# ESP32_SCH.net
KiCad netlist of a schematic drawn in Altium Designer
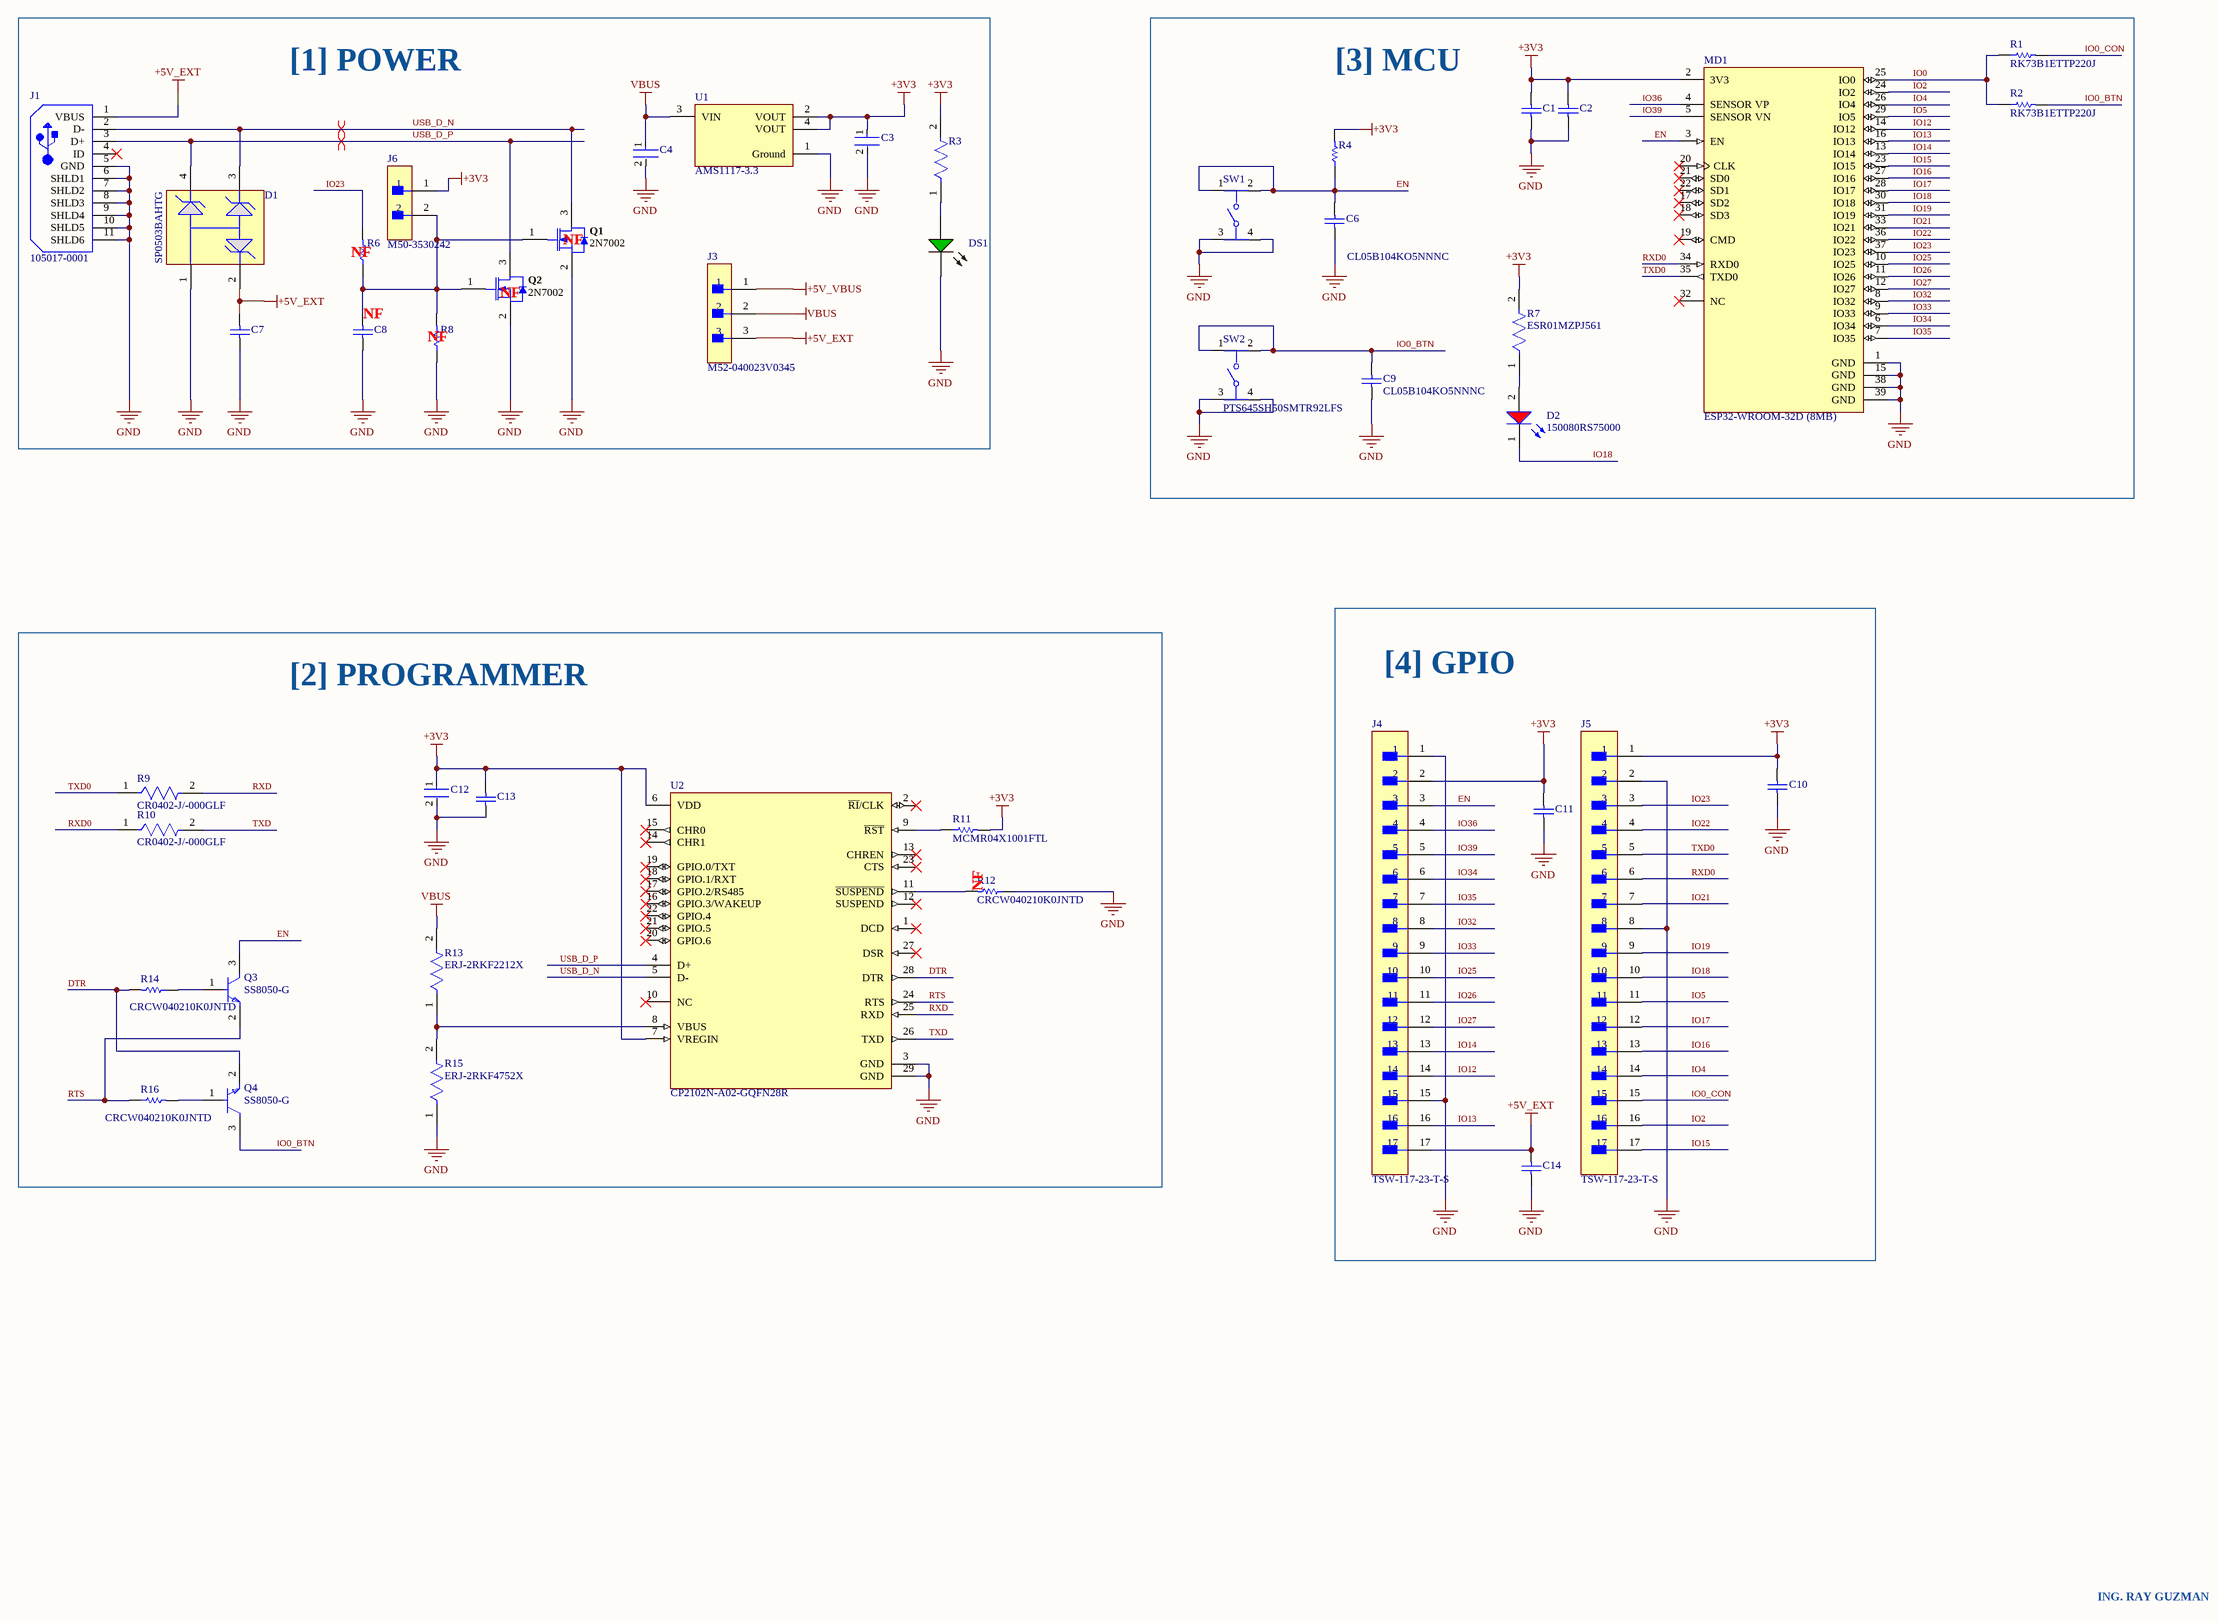
[diagram p0: ESP32_SCH.SchDoc]

(export (version "E")
  (design (tool "Eeschema 10.0.6"))
  (components
    (comp (ref "C1")
      (value "CL21A226MAQNNNE")
      (footprint "CAPC2013X140X45LL15T25")
      (description "Multi-layer Ceramic Capacitor, 22 uF, -55 to 85 degC, 2-Pin SMD (0805), RoHS, Tape and Reel")
      (fields (field (name "MANUFACTURER") "Samsung Electro-Mechanics") (field (name "TOLERANCE") "±20%"))
      (libsource (lib "Altium Content Vault") (part "CAP-NP-2"))
    )
    (comp (ref "C2")
      (value "CL05B104KO5NNNC")
      (footprint "CAPC1050X55X23ML05T13")
      (description "Chip Capacitor, 100 nF, +/- 10%, 16 V, -55 to 125 degC, 0402 (1005 Metric), RoHS, Tape and Reel")
      (fields (field (name "MANUFACTURER") "Samsung Electro-Mechanics"))
      (libsource (lib "Altium Content Vault") (part "CAP-NP-2"))
    )
    (comp (ref "C3")
      (value "CL05A106MP5NUNC")
      (footprint "FP-CL05A106MP5NUNC-MFG")
      (description "CAP CER 10UF 10V X5R 0402")
      (fields
        (field (name "OCTOPART") "https://octopart.com/cl05a106mp5nunc-samsung-22457395")
        (field (name "TOLERANCE") "20%")
      )
      (libsource (lib "Altium Content Vault") (part "b4654b650e69147ec39a6b967a45e02"))
    )
    (comp (ref "C4")
      (value "CL05A106MP5NUNC")
      (footprint "FP-CL05A106MP5NUNC-MFG")
      (description "CAP CER 10UF 10V X5R 0402")
      (fields
        (field (name "OCTOPART") "https://octopart.com/cl05a106mp5nunc-samsung-22457395")
        (field (name "TOLERANCE") "20%")
      )
      (libsource (lib "Altium Content Vault") (part "b4654b650e69147ec39a6b967a45e02"))
    )
    (comp (ref "C6")
      (value "CL05B104KO5NNNC")
      (footprint "CAPC1050X55X23ML05T13")
      (description "Chip Capacitor, 100 nF, +/- 10%, 16 V, -55 to 125 degC, 0402 (1005 Metric), RoHS, Tape and Reel")
      (fields (field (name "MANUFACTURER") "Samsung Electro-Mechanics"))
      (libsource (lib "Altium Content Vault") (part "CAP-NP-2"))
    )
    (comp (ref "C7")
      (value "CL05B104KO5NNNC")
      (footprint "CAPC1050X55X23ML05T13")
      (description "Chip Capacitor, 100 nF, +/- 10%, 16 V, -55 to 125 degC, 0402 (1005 Metric), RoHS, Tape and Reel")
      (fields (field (name "MANUFACTURER") "Samsung Electro-Mechanics"))
      (libsource (lib "Altium Content Vault") (part "CAP-NP-2"))
    )
    (comp (ref "C8")
      (value "CL05B104KO5NNNC")
      (footprint "CAPC1050X55X23ML05T13")
      (description "Chip Capacitor, 100 nF, +/- 10%, 16 V, -55 to 125 degC, 0402 (1005 Metric), RoHS, Tape and Reel")
      (fields (field (name "MANUFACTURER") "Samsung Electro-Mechanics"))
      (libsource (lib "Altium Content Vault") (part "CAP-NP-2"))
    )
    (comp (ref "C9")
      (value "CL05B104KO5NNNC")
      (footprint "CAPC1050X55X23ML05T13")
      (description "Chip Capacitor, 100 nF, +/- 10%, 16 V, -55 to 125 degC, 0402 (1005 Metric), RoHS, Tape and Reel")
      (fields (field (name "MANUFACTURER") "Samsung Electro-Mechanics"))
      (libsource (lib "Altium Content Vault") (part "CAP-NP-2"))
    )
    (comp (ref "C10")
      (value "CL05B104KO5NNNC")
      (footprint "CAPC1050X55X23ML05T13")
      (description "Chip Capacitor, 100 nF, +/- 10%, 16 V, -55 to 125 degC, 0402 (1005 Metric), RoHS, Tape and Reel")
      (fields (field (name "MANUFACTURER") "Samsung Electro-Mechanics"))
      (libsource (lib "Altium Content Vault") (part "CAP-NP-2"))
    )
    (comp (ref "C11")
      (value "CL05B104KO5NNNC")
      (footprint "CAPC1050X55X23ML05T13")
      (description "Chip Capacitor, 100 nF, +/- 10%, 16 V, -55 to 125 degC, 0402 (1005 Metric), RoHS, Tape and Reel")
      (fields (field (name "MANUFACTURER") "Samsung Electro-Mechanics"))
      (libsource (lib "Altium Content Vault") (part "CAP-NP-2"))
    )
    (comp (ref "C12")
      (value "C1005X5R1A475K050BC")
      (footprint "FP-C1005-050-0_15-MFG")
      (description "CAP CER 4.7UF 10V X5R 0402")
      (fields (field (name "TOLERANCE") "10%"))
      (libsource (lib "Altium Content Vault") (part "b4654b650e69147ec39a6b967a45e02"))
    )
    (comp (ref "C13")
      (value "CL05B104KO5NNNC")
      (footprint "CAPC1050X55X23ML05T13")
      (description "Chip Capacitor, 100 nF, +/- 10%, 16 V, -55 to 125 degC, 0402 (1005 Metric), RoHS, Tape and Reel")
      (fields (field (name "MANUFACTURER") "Samsung Electro-Mechanics"))
      (libsource (lib "Altium Content Vault") (part "CAP-NP-2"))
    )
    (comp (ref "C14")
      (value "CL05B104KO5NNNC")
      (footprint "CAPC1050X55X23ML05T13")
      (description "Chip Capacitor, 100 nF, +/- 10%, 16 V, -55 to 125 degC, 0402 (1005 Metric), RoHS, Tape and Reel")
      (fields (field (name "MANUFACTURER") "Samsung Electro-Mechanics"))
      (libsource (lib "Altium Content Vault") (part "CAP-NP-2"))
    )
    (comp (ref "D1")
      (value "SP0503BAHTG")
      (footprint "LFUS-SOT143-4_V")
      (description "TVS Diode Array, 30 pF, 30 KV, -40 to 85 degC, 4-Pin SOT143, RoHS, Tape and Reel")
      (fields (field (name "MANUFACTURER") "Littelfuse"))
      (libsource (lib "Altium Content Vault") (part "LFUS-SP0503BAHTG-SOT143-4"))
    )
    (comp (ref "D2")
      (value "150080RS75000")
      (footprint "WL-SMCW_0805_150080xx75000")
      (libsource (lib "Altium Content Vault") (part "LED_Red_2A-1K"))
    )
    (comp (ref "DS1")
      (value "HSMG-C170")
      (footprint "AVAG-HSMX-C170_V")
      (description "Chip LED, Green, 2.2 V, -40 to 85 degC, 2-Pin SMD, Pb-Free, Tape and Reel")
      (fields (field (name "MANUFACTURER") "Avago"))
      (libsource (lib "Altium Content Vault") (part "LED_GREEN_A1K2-2"))
    )
    (comp (ref "J1")
      (value "105017-0001")
      (footprint "USB-MICRO-B_V")
      (fields (field (name "MANUFACTURER") "Molex"))
      (libsource (lib "Altium Content Vault") (part "USB-5-6SHLD"))
    )
    (comp (ref "J3")
      (value "M52-040023V0345")
      (footprint "FP-M52-040023V0345-MFG")
      (description "CONN HEADER VERT 3POS 1.27MM")
      (libsource (lib "Altium Content Vault") (part "d6a96a410146d2d686cfe982f2af7ec"))
    )
    (comp (ref "J4")
      (value "TSW-117-23-T-S")
      (footprint "FP-TSW-117-23-T-S-MFG")
      (description "CONN HEADER VERT 17POS 2.54MM")
      (libsource (lib "Altium Content Vault") (part "0c150866fb6c9bc24cbcca335282b40"))
    )
    (comp (ref "J5")
      (value "TSW-117-23-T-S")
      (footprint "FP-TSW-117-23-T-S-MFG")
      (description "CONN HEADER VERT 17POS 2.54MM")
      (libsource (lib "Altium Content Vault") (part "0c150866fb6c9bc24cbcca335282b40"))
    )
    (comp (ref "J6")
      (value "M50-3530242")
      (footprint "FP-M50-3530242-MFG")
      (description "CONN HEADER VERT 2POS 1.27MM")
      (libsource (lib "Altium Content Vault") (part "3bc925449376181038e59eaffc5286c"))
    )
    (comp (ref "MD1")
      (value "ESP32-WROOM-32D (8MB)")
      (footprint "FP-ESP32-WROOM-32D_8MB-MFG")
      (description "RX TXRX MOD WIFI TRACE ANT SMD")
      (libsource (lib "Altium Content Vault") (part "f49400bffd2bcd917121b26d8c3f628"))
    )
    (comp (ref "Q1")
      (value "2N7002")
      (footprint "INF-PG-SOT23_M")
      (fields (field (name "MANUFACTURER") "Infineon"))
      (libsource (lib "Altium Content Vault") (part "INF-NDMOS-GSD-3"))
    )
    (comp (ref "Q2")
      (value "2N7002")
      (footprint "INF-PG-SOT23_M")
      (fields (field (name "MANUFACTURER") "Infineon"))
      (libsource (lib "Altium Content Vault") (part "INF-NDMOS-GSD-3"))
    )
    (comp (ref "Q3")
      (value "SS8050-G")
      (footprint "FP-SS8050-G-MFG")
      (description "NPN TRANSISTOR 1.5A 40V SOT-23 R")
      (libsource (lib "Altium Content Vault") (part "2a1388f82443b098dcd57d24ac7632d"))
    )
    (comp (ref "Q4")
      (value "SS8050-G")
      (footprint "FP-SS8050-G-MFG")
      (description "NPN TRANSISTOR 1.5A 40V SOT-23 R")
      (libsource (lib "Altium Content Vault") (part "2a1388f82443b098dcd57d24ac7632d"))
    )
    (comp (ref "R1")
      (value "RK73B1ETTP220J")
      (footprint "RESC1005X40X25ML10T10")
      (fields (field (name "MANUFACTURER") "KOA Speer"))
      (libsource (lib "Altium Content Vault") (part "RES"))
    )
    (comp (ref "R2")
      (value "RK73B1ETTP220J")
      (footprint "RESC1005X40X25ML10T10")
      (fields (field (name "MANUFACTURER") "KOA Speer"))
      (libsource (lib "Altium Content Vault") (part "RES"))
    )
    (comp (ref "R3")
      (value "PNM0402E5001BST1")
      (footprint "FP-PNM0402-IPC_C")
      (description "RES SMD 5K OHM 0.1% 1/20W 0402")
      (fields (field (name "TOLERANCE") "0.1%"))
      (libsource (lib "Altium Content Vault") (part "1029c3af85768c4190bb7ad29bc67b5"))
    )
    (comp (ref "R4")
      (value "CRCW040210K0JNTD")
      (footprint "RESC1005X40X25ML05T05")
      (fields (field (name "MANUFACTURER") "Vishay Dale"))
      (libsource (lib "Altium Content Vault") (part "RES"))
    )
    (comp (ref "R6")
      (value "MCMR04X1001FTL")
      (footprint "RESC1005X40X25ML05T10")
      (fields (field (name "MANUFACTURER") "Multicomp"))
      (libsource (lib "Altium Content Vault") (part "RES"))
    )
    (comp (ref "R7")
      (value "ESR01MZPJ561")
      (footprint "FP-ESR01-IPC_C")
      (description "560Ω ±5% 0.2W 0402 Anti-Surge Chip Resistor AEC-Q200")
      (fields (field (name "TOLERANCE") "5%"))
      (libsource (lib "Altium Content Vault") (part "1029c3af85768c4190bb7ad29bc67b5"))
    )
    (comp (ref "R8")
      (value "CRCW040210K0JNTD")
      (footprint "RESC1005X40X25ML05T05")
      (fields (field (name "MANUFACTURER") "Vishay Dale"))
      (libsource (lib "Altium Content Vault") (part "RES"))
    )
    (comp (ref "R9")
      (value "CR0402-J/-000GLF")
      (footprint "FP-CR0402-IPC_B")
      (description "Thick Film Chip Resistors 0402 0Ω 0.0625W 5%")
      (fields (field (name "TOLERANCE") "5%"))
      (libsource (lib "Altium Content Vault") (part "1029c3af85768c4190bb7ad29bc67b5"))
    )
    (comp (ref "R10")
      (value "CR0402-J/-000GLF")
      (footprint "FP-CR0402-IPC_B")
      (description "Thick Film Chip Resistors 0402 0Ω 0.0625W 5%")
      (fields (field (name "TOLERANCE") "5%"))
      (libsource (lib "Altium Content Vault") (part "1029c3af85768c4190bb7ad29bc67b5"))
    )
    (comp (ref "R11")
      (value "MCMR04X1001FTL")
      (footprint "RESC1005X40X25ML05T10")
      (fields (field (name "MANUFACTURER") "Multicomp"))
      (libsource (lib "Altium Content Vault") (part "RES"))
    )
    (comp (ref "R12")
      (value "CRCW040210K0JNTD")
      (footprint "RESC1005X40X25ML05T05")
      (fields (field (name "MANUFACTURER") "Vishay Dale"))
      (libsource (lib "Altium Content Vault") (part "RES"))
    )
    (comp (ref "R13")
      (value "ERJ-2RKF2212X")
      (footprint "FP-ERJ2RK-IPC_C")
      (description "RES SMD 22.1K OHM 1% 1/10W 0402")
      (fields (field (name "TOLERANCE") "1%"))
      (libsource (lib "Altium Content Vault") (part "1029c3af85768c4190bb7ad29bc67b5"))
    )
    (comp (ref "R14")
      (value "CRCW040210K0JNTD")
      (footprint "RESC1005X40X25ML05T05")
      (fields (field (name "MANUFACTURER") "Vishay Dale"))
      (libsource (lib "Altium Content Vault") (part "RES"))
    )
    (comp (ref "R15")
      (value "ERJ-2RKF4752X")
      (footprint "FP-ERJ2RK-IPC_A")
      (description "RES SMD 47.5K OHM 1% 1/10W 0402")
      (fields (field (name "TOLERANCE") "1%"))
      (libsource (lib "Altium Content Vault") (part "1029c3af85768c4190bb7ad29bc67b5"))
    )
    (comp (ref "R16")
      (value "CRCW040210K0JNTD")
      (footprint "RESC1005X40X25ML05T05")
      (fields (field (name "MANUFACTURER") "Vishay Dale"))
      (libsource (lib "Altium Content Vault") (part "RES"))
    )
    (comp (ref "SW1")
      (value "PTS645SH50SMTR92LFS")
      (footprint "FP-PTS645SH50SMTR92LFS-MFG")
      (description "SWITCH TACTILE SPST-NO 0.05A 12V")
      (libsource (lib "Altium Content Vault") (part "1adf0dd01260c80cf25a44bfd6b99ba"))
    )
    (comp (ref "SW2")
      (value "PTS645SH50SMTR92LFS")
      (footprint "FP-PTS645SH50SMTR92LFS-MFG")
      (description "SWITCH TACTILE SPST-NO 0.05A 12V")
      (libsource (lib "Altium Content Vault") (part "1adf0dd01260c80cf25a44bfd6b99ba"))
    )
    (comp (ref "U1")
      (value "AMS1117-3.3")
      (footprint "FP-AMS1117-IPC_C")
      (description "LDO Voltage Regulators 1A, 3.3V")
      (fields
        (field (name "OCTOPART") "https://octopart.com/ams1117-3.3-advanced+monolithic+systems-25899300")
        (field (name "MANUFACTURER") "Advanced Monolithic Systems")
      )
      (libsource (lib "Altium Content Vault") (part "8bdbb5f8e77002000e30dd2845d0354"))
    )
    (comp (ref "U2")
      (value "CP2102N-A02-GQFN28R")
      (footprint "FP-CP2102N-A02-GQFN28R-MFG")
      (description "IC USB TO UART BRIDGE QFN28")
      (libsource (lib "Altium Content Vault") (part "670edaef084fb69d2a747396d70a05e"))
    )
  )
  (nets
    (net (code "1") (name "+3V3") (class "Default")
      (node (ref "C1") (pin "1") (pinfunction "1_1") (pintype "passive"))
      (node (ref "C10") (pin "1") (pinfunction "1_1") (pintype "passive"))
      (node (ref "C11") (pin "1") (pinfunction "1_1") (pintype "passive"))
      (node (ref "C12") (pin "1") (pinfunction "1_1") (pintype "passive"))
      (node (ref "C13") (pin "1") (pinfunction "1_1") (pintype "passive"))
      (node (ref "C2") (pin "1") (pinfunction "1_1") (pintype "passive"))
      (node (ref "C3") (pin "1") (pinfunction "1_1") (pintype "passive"))
      (node (ref "J4") (pin "2") (pinfunction "2_2") (pintype "passive"))
      (node (ref "J5") (pin "1") (pinfunction "1_1") (pintype "passive"))
      (node (ref "J6") (pin "1") (pinfunction "1_1") (pintype "passive"))
      (node (ref "MD1") (pin "2") (pinfunction "3V3_2") (pintype "power_in"))
      (node (ref "R11") (pin "2") (pinfunction "2_2") (pintype "passive"))
      (node (ref "R3") (pin "2") (pinfunction "2_2") (pintype "passive"))
      (node (ref "R4") (pin "2") (pinfunction "2_2") (pintype "passive"))
      (node (ref "R7") (pin "2") (pinfunction "2_2") (pintype "passive"))
      (node (ref "U1") (pin "2") (pinfunction "VOUT_2") (pintype "passive"))
      (node (ref "U1") (pin "4") (pinfunction "VOUT_4") (pintype "passive"))
      (node (ref "U2") (pin "6") (pinfunction "VDD_6") (pintype "power_in"))
      (node (ref "U2") (pin "7") (pinfunction "VREGIN_7") (pintype "input"))
    )
    (net (code "2") (name "+5V_EXT") (class "Default")
      (node (ref "C14") (pin "1") (pinfunction "1_1") (pintype "passive"))
      (node (ref "C7") (pin "1") (pinfunction "1_1") (pintype "passive"))
      (node (ref "D1") (pin "2") (pinfunction "2_2") (pintype "passive"))
      (node (ref "J1") (pin "1") (pinfunction "VBUS_1") (pintype "passive"))
      (node (ref "J3") (pin "3") (pinfunction "3_3") (pintype "passive"))
      (node (ref "J4") (pin "17") (pinfunction "17_17") (pintype "passive"))
    )
    (net (code "3") (name "+5V_VBUS") (class "Default")
      (node (ref "J3") (pin "1") (pinfunction "1_1") (pintype "passive"))
    )
    (net (code "4") (name "/DTR") (class "Default")
      (node (ref "Q4") (pin "2") (pinfunction "E_2") (pintype "passive"))
      (node (ref "R14") (pin "2") (pinfunction "2_2") (pintype "passive"))
      (node (ref "U2") (pin "28") (pinfunction "DTR_28") (pintype "output"))
    )
    (net (code "5") (name "/EN") (class "Default")
      (node (ref "C6") (pin "2") (pinfunction "2_2") (pintype "passive"))
      (node (ref "J4") (pin "3") (pinfunction "3_3") (pintype "passive"))
      (node (ref "MD1") (pin "3") (pinfunction "EN_3") (pintype "input"))
      (node (ref "Q3") (pin "3") (pinfunction "C_3") (pintype "passive"))
      (node (ref "R4") (pin "1") (pinfunction "1_1") (pintype "passive"))
      (node (ref "SW1") (pin "1") (pinfunction "1_1") (pintype "passive"))
      (node (ref "SW1") (pin "2") (pinfunction "2_2") (pintype "passive"))
    )
    (net (code "6") (name "/IO0") (class "Default")
      (node (ref "MD1") (pin "25") (pinfunction "IO0_25") (pintype "bidirectional"))
      (node (ref "R1") (pin "1") (pinfunction "1_1") (pintype "passive"))
      (node (ref "R2") (pin "1") (pinfunction "1_1") (pintype "passive"))
    )
    (net (code "7") (name "/IO0_BTN") (class "Default")
      (node (ref "C9") (pin "2") (pinfunction "2_2") (pintype "passive"))
      (node (ref "Q4") (pin "3") (pinfunction "C_3") (pintype "passive"))
      (node (ref "R2") (pin "2") (pinfunction "2_2") (pintype "passive"))
      (node (ref "SW2") (pin "1") (pinfunction "1_1") (pintype "passive"))
      (node (ref "SW2") (pin "2") (pinfunction "2_2") (pintype "passive"))
    )
    (net (code "8") (name "/IO0_CON") (class "Default")
      (node (ref "J5") (pin "15") (pinfunction "15_15") (pintype "passive"))
      (node (ref "R1") (pin "2") (pinfunction "2_2") (pintype "passive"))
    )
    (net (code "9") (name "/IO2") (class "Default")
      (node (ref "J5") (pin "16") (pinfunction "16_16") (pintype "passive"))
      (node (ref "MD1") (pin "24") (pinfunction "IO2_24") (pintype "bidirectional"))
    )
    (net (code "10") (name "/IO4") (class "Default")
      (node (ref "J5") (pin "14") (pinfunction "14_14") (pintype "passive"))
      (node (ref "MD1") (pin "26") (pinfunction "IO4_26") (pintype "bidirectional"))
    )
    (net (code "11") (name "/IO5") (class "Default")
      (node (ref "J5") (pin "11") (pinfunction "11_11") (pintype "passive"))
      (node (ref "MD1") (pin "29") (pinfunction "IO5_29") (pintype "bidirectional"))
    )
    (net (code "12") (name "/IO12") (class "Default")
      (node (ref "J4") (pin "14") (pinfunction "14_14") (pintype "passive"))
      (node (ref "MD1") (pin "14") (pinfunction "IO12_14") (pintype "bidirectional"))
    )
    (net (code "13") (name "/IO13") (class "Default")
      (node (ref "J4") (pin "16") (pinfunction "16_16") (pintype "passive"))
      (node (ref "MD1") (pin "16") (pinfunction "IO13_16") (pintype "bidirectional"))
    )
    (net (code "14") (name "/IO14") (class "Default")
      (node (ref "J4") (pin "13") (pinfunction "13_13") (pintype "passive"))
      (node (ref "MD1") (pin "13") (pinfunction "IO14_13") (pintype "bidirectional"))
    )
    (net (code "15") (name "/IO15") (class "Default")
      (node (ref "J5") (pin "17") (pinfunction "17_17") (pintype "passive"))
      (node (ref "MD1") (pin "23") (pinfunction "IO15_23") (pintype "bidirectional"))
    )
    (net (code "16") (name "/IO16") (class "Default")
      (node (ref "J5") (pin "13") (pinfunction "13_13") (pintype "passive"))
      (node (ref "MD1") (pin "27") (pinfunction "IO16_27") (pintype "bidirectional"))
    )
    (net (code "17") (name "/IO17") (class "Default")
      (node (ref "J5") (pin "12") (pinfunction "12_12") (pintype "passive"))
      (node (ref "MD1") (pin "28") (pinfunction "IO17_28") (pintype "bidirectional"))
    )
    (net (code "18") (name "/IO18") (class "Default")
      (node (ref "D2") (pin "1") (pinfunction "K_1") (pintype "passive"))
      (node (ref "J5") (pin "10") (pinfunction "10_10") (pintype "passive"))
      (node (ref "MD1") (pin "30") (pinfunction "IO18_30") (pintype "bidirectional"))
    )
    (net (code "19") (name "/IO19") (class "Default")
      (node (ref "J5") (pin "9") (pinfunction "9_9") (pintype "passive"))
      (node (ref "MD1") (pin "31") (pinfunction "IO19_31") (pintype "bidirectional"))
    )
    (net (code "20") (name "/IO21") (class "Default")
      (node (ref "J5") (pin "7") (pinfunction "7_7") (pintype "passive"))
      (node (ref "MD1") (pin "33") (pinfunction "IO21_33") (pintype "bidirectional"))
    )
    (net (code "21") (name "/IO22") (class "Default")
      (node (ref "J5") (pin "4") (pinfunction "4_4") (pintype "passive"))
      (node (ref "MD1") (pin "36") (pinfunction "IO22_36") (pintype "bidirectional"))
    )
    (net (code "22") (name "/IO23") (class "Default")
      (node (ref "J5") (pin "3") (pinfunction "3_3") (pintype "passive"))
      (node (ref "MD1") (pin "37") (pinfunction "IO23_37") (pintype "bidirectional"))
      (node (ref "R6") (pin "2") (pinfunction "2_2") (pintype "passive"))
    )
    (net (code "23") (name "/IO25") (class "Default")
      (node (ref "J4") (pin "10") (pinfunction "10_10") (pintype "passive"))
      (node (ref "MD1") (pin "10") (pinfunction "IO25_10") (pintype "bidirectional"))
    )
    (net (code "24") (name "/IO26") (class "Default")
      (node (ref "J4") (pin "11") (pinfunction "11_11") (pintype "passive"))
      (node (ref "MD1") (pin "11") (pinfunction "IO26_11") (pintype "bidirectional"))
    )
    (net (code "25") (name "/IO27") (class "Default")
      (node (ref "J4") (pin "12") (pinfunction "12_12") (pintype "passive"))
      (node (ref "MD1") (pin "12") (pinfunction "IO27_12") (pintype "bidirectional"))
    )
    (net (code "26") (name "/IO32") (class "Default")
      (node (ref "J4") (pin "8") (pinfunction "8_8") (pintype "passive"))
      (node (ref "MD1") (pin "8") (pinfunction "IO32_8") (pintype "bidirectional"))
    )
    (net (code "27") (name "/IO33") (class "Default")
      (node (ref "J4") (pin "9") (pinfunction "9_9") (pintype "passive"))
      (node (ref "MD1") (pin "9") (pinfunction "IO33_9") (pintype "bidirectional"))
    )
    (net (code "28") (name "/IO34") (class "Default")
      (node (ref "J4") (pin "6") (pinfunction "6_6") (pintype "passive"))
      (node (ref "MD1") (pin "6") (pinfunction "IO34_6") (pintype "bidirectional"))
    )
    (net (code "29") (name "/IO35") (class "Default")
      (node (ref "J4") (pin "7") (pinfunction "7_7") (pintype "passive"))
      (node (ref "MD1") (pin "7") (pinfunction "IO35_7") (pintype "bidirectional"))
    )
    (net (code "30") (name "/IO36") (class "Default")
      (node (ref "J4") (pin "4") (pinfunction "4_4") (pintype "passive"))
      (node (ref "MD1") (pin "4") (pinfunction "SENSOR_VP_4") (pintype "passive"))
    )
    (net (code "31") (name "/IO39") (class "Default")
      (node (ref "J4") (pin "5") (pinfunction "5_5") (pintype "passive"))
      (node (ref "MD1") (pin "5") (pinfunction "SENSOR_VN_5") (pintype "passive"))
    )
    (net (code "32") (name "/RTS") (class "Default")
      (node (ref "Q3") (pin "2") (pinfunction "E_2") (pintype "passive"))
      (node (ref "R16") (pin "1") (pinfunction "1_1") (pintype "passive"))
      (node (ref "U2") (pin "24") (pinfunction "RTS_24") (pintype "output"))
    )
    (net (code "33") (name "/RXD") (class "Default")
      (node (ref "R9") (pin "2") (pinfunction "2_2") (pintype "passive"))
      (node (ref "U2") (pin "25") (pinfunction "RXD_25") (pintype "input"))
    )
    (net (code "34") (name "/RXD0") (class "Default")
      (node (ref "J5") (pin "6") (pinfunction "6_6") (pintype "passive"))
      (node (ref "MD1") (pin "34") (pinfunction "RXD0_34") (pintype "input"))
      (node (ref "R10") (pin "1") (pinfunction "1_1") (pintype "passive"))
    )
    (net (code "35") (name "/TXD") (class "Default")
      (node (ref "R10") (pin "2") (pinfunction "2_2") (pintype "passive"))
      (node (ref "U2") (pin "26") (pinfunction "TXD_26") (pintype "output"))
    )
    (net (code "36") (name "/TXD0") (class "Default")
      (node (ref "J5") (pin "5") (pinfunction "5_5") (pintype "passive"))
      (node (ref "MD1") (pin "35") (pinfunction "TXD0_35") (pintype "output"))
      (node (ref "R9") (pin "1") (pinfunction "1_1") (pintype "passive"))
    )
    (net (code "37") (name "/USB_D_N") (class "Default")
      (node (ref "D1") (pin "3") (pinfunction "3_3") (pintype "passive"))
      (node (ref "J1") (pin "2") (pinfunction "D-_2") (pintype "passive"))
      (node (ref "Q1") (pin "3") (pinfunction "DRAIN_3") (pintype "passive"))
      (node (ref "U2") (pin "5") (pinfunction "D-_5") (pintype "passive"))
    )
    (net (code "38") (name "/USB_D_P") (class "Default")
      (node (ref "D1") (pin "4") (pinfunction "4_4") (pintype "passive"))
      (node (ref "J1") (pin "3") (pinfunction "D+_3") (pintype "passive"))
      (node (ref "Q2") (pin "3") (pinfunction "DRAIN_3") (pintype "passive"))
      (node (ref "U2") (pin "4") (pinfunction "D+_4") (pintype "passive"))
    )
    (net (code "39") (name "GND") (class "Default")
      (node (ref "C1") (pin "2") (pinfunction "2_2") (pintype "passive"))
      (node (ref "C10") (pin "2") (pinfunction "2_2") (pintype "passive"))
      (node (ref "C11") (pin "2") (pinfunction "2_2") (pintype "passive"))
      (node (ref "C12") (pin "2") (pinfunction "2_2") (pintype "passive"))
      (node (ref "C13") (pin "2") (pinfunction "2_2") (pintype "passive"))
      (node (ref "C14") (pin "2") (pinfunction "2_2") (pintype "passive"))
      (node (ref "C2") (pin "2") (pinfunction "2_2") (pintype "passive"))
      (node (ref "C3") (pin "2") (pinfunction "2_2") (pintype "passive"))
      (node (ref "C4") (pin "2") (pinfunction "2_2") (pintype "passive"))
      (node (ref "C6") (pin "1") (pinfunction "1_1") (pintype "passive"))
      (node (ref "C7") (pin "2") (pinfunction "2_2") (pintype "passive"))
      (node (ref "C8") (pin "1") (pinfunction "1_1") (pintype "passive"))
      (node (ref "C9") (pin "1") (pinfunction "1_1") (pintype "passive"))
      (node (ref "D1") (pin "1") (pinfunction "1_1") (pintype "passive"))
      (node (ref "DS1") (pin "2") (pinfunction "K_2") (pintype "passive"))
      (node (ref "J1") (pin "10") (pinfunction "SHLD5_10") (pintype "passive"))
      (node (ref "J1") (pin "11") (pinfunction "SHLD6_11") (pintype "passive"))
      (node (ref "J1") (pin "5") (pinfunction "GND_5") (pintype "passive"))
      (node (ref "J1") (pin "6") (pinfunction "SHLD1_6") (pintype "passive"))
      (node (ref "J1") (pin "7") (pinfunction "SHLD2_7") (pintype "passive"))
      (node (ref "J1") (pin "8") (pinfunction "SHLD3_8") (pintype "passive"))
      (node (ref "J1") (pin "9") (pinfunction "SHLD4_9") (pintype "passive"))
      (node (ref "J4") (pin "1") (pinfunction "1_1") (pintype "passive"))
      (node (ref "J4") (pin "15") (pinfunction "15_15") (pintype "passive"))
      (node (ref "J5") (pin "2") (pinfunction "2_2") (pintype "passive"))
      (node (ref "J5") (pin "8") (pinfunction "8_8") (pintype "passive"))
      (node (ref "MD1") (pin "1") (pinfunction "GND_1") (pintype "power_in"))
      (node (ref "MD1") (pin "15") (pinfunction "GND_15") (pintype "power_in"))
      (node (ref "MD1") (pin "38") (pinfunction "GND_38") (pintype "power_in"))
      (node (ref "MD1") (pin "39") (pinfunction "GND_39") (pintype "power_in"))
      (node (ref "Q1") (pin "2") (pinfunction "SOURCE_2") (pintype "passive"))
      (node (ref "Q2") (pin "2") (pinfunction "SOURCE_2") (pintype "passive"))
      (node (ref "R12") (pin "1") (pinfunction "1_1") (pintype "passive"))
      (node (ref "R15") (pin "1") (pinfunction "1_1") (pintype "passive"))
      (node (ref "R8") (pin "1") (pinfunction "1_1") (pintype "passive"))
      (node (ref "SW1") (pin "3") (pinfunction "3_3") (pintype "passive"))
      (node (ref "SW1") (pin "4") (pinfunction "4_4") (pintype "passive"))
      (node (ref "SW2") (pin "3") (pinfunction "3_3") (pintype "passive"))
      (node (ref "SW2") (pin "4") (pinfunction "4_4") (pintype "passive"))
      (node (ref "U1") (pin "1") (pinfunction "Ground_1") (pintype "power_in"))
      (node (ref "U2") (pin "29") (pinfunction "GND_29") (pintype "power_in"))
      (node (ref "U2") (pin "3") (pinfunction "GND_3") (pintype "power_in"))
    )
    (net (code "40") (name "Net-(D2-A)") (class "Default")
      (node (ref "D2") (pin "2") (pinfunction "A_2") (pintype "passive"))
      (node (ref "R7") (pin "1") (pinfunction "1_1") (pintype "passive"))
    )
    (net (code "41") (name "Net-(DS1-A)") (class "Default")
      (node (ref "DS1") (pin "1") (pinfunction "A_1") (pintype "passive"))
      (node (ref "R3") (pin "1") (pinfunction "1_1") (pintype "passive"))
    )
    (net (code "42") (name "Net-(Q1-GATE)") (class "Default")
      (node (ref "C8") (pin "2") (pinfunction "2_2") (pintype "passive"))
      (node (ref "J6") (pin "2") (pinfunction "2_2") (pintype "passive"))
      (node (ref "Q1") (pin "1") (pinfunction "GATE_1") (pintype "passive"))
      (node (ref "Q2") (pin "1") (pinfunction "GATE_1") (pintype "passive"))
      (node (ref "R6") (pin "1") (pinfunction "1_1") (pintype "passive"))
      (node (ref "R8") (pin "2") (pinfunction "2_2") (pintype "passive"))
    )
    (net (code "43") (name "Net-(Q3-B)") (class "Default")
      (node (ref "Q3") (pin "1") (pinfunction "B_1") (pintype "passive"))
      (node (ref "R14") (pin "1") (pinfunction "1_1") (pintype "passive"))
    )
    (net (code "44") (name "Net-(Q4-B)") (class "Default")
      (node (ref "Q4") (pin "1") (pinfunction "B_1") (pintype "passive"))
      (node (ref "R16") (pin "2") (pinfunction "2_2") (pintype "passive"))
    )
    (net (code "45") (name "Net-(U2-VBUS)") (class "Default")
      (node (ref "R13") (pin "1") (pinfunction "1_1") (pintype "passive"))
      (node (ref "R15") (pin "2") (pinfunction "2_2") (pintype "passive"))
      (node (ref "U2") (pin "8") (pinfunction "VBUS_8") (pintype "input"))
    )
    (net (code "46") (name "Net-(U2-~{RST})") (class "Default")
      (node (ref "R11") (pin "1") (pinfunction "1_1") (pintype "passive"))
      (node (ref "U2") (pin "9") (pinfunction "~{RST}_9") (pintype "input"))
    )
    (net (code "47") (name "Net-(U2-~{SUSPEND})") (class "Default")
      (node (ref "R12") (pin "2") (pinfunction "2_2") (pintype "passive"))
      (node (ref "U2") (pin "11") (pinfunction "~{SUSPEND}_11") (pintype "output"))
    )
    (net (code "48") (name "VBUS") (class "Default")
      (node (ref "C4") (pin "1") (pinfunction "1_1") (pintype "passive"))
      (node (ref "J3") (pin "2") (pinfunction "2_2") (pintype "passive"))
      (node (ref "R13") (pin "2") (pinfunction "2_2") (pintype "passive"))
      (node (ref "U1") (pin "3") (pinfunction "VIN_3") (pintype "power_in"))
    )
    (net (code "49") (name "unconnected-(J1-ID-Pad4)") (class "Default")
      (node (ref "J1") (pin "4") (pinfunction "ID_4") (pintype "passive+no_connect"))
    )
    (net (code "50") (name "unconnected-(MD1-CLK-Pad20)") (class "Default")
      (node (ref "MD1") (pin "20") (pinfunction "CLK_20") (pintype "input+no_connect"))
    )
    (net (code "51") (name "unconnected-(MD1-CMD-Pad19)") (class "Default")
      (node (ref "MD1") (pin "19") (pinfunction "CMD_19") (pintype "bidirectional+no_connect"))
    )
    (net (code "52") (name "unconnected-(MD1-NC-Pad32)") (class "Default")
      (node (ref "MD1") (pin "32") (pinfunction "NC_32") (pintype "passive+no_connect"))
    )
    (net (code "53") (name "unconnected-(MD1-SD0-Pad21)") (class "Default")
      (node (ref "MD1") (pin "21") (pinfunction "SD0_21") (pintype "bidirectional+no_connect"))
    )
    (net (code "54") (name "unconnected-(MD1-SD1-Pad22)") (class "Default")
      (node (ref "MD1") (pin "22") (pinfunction "SD1_22") (pintype "bidirectional+no_connect"))
    )
    (net (code "55") (name "unconnected-(MD1-SD2-Pad17)") (class "Default")
      (node (ref "MD1") (pin "17") (pinfunction "SD2_17") (pintype "bidirectional+no_connect"))
    )
    (net (code "56") (name "unconnected-(MD1-SD3-Pad18)") (class "Default")
      (node (ref "MD1") (pin "18") (pinfunction "SD3_18") (pintype "bidirectional+no_connect"))
    )
    (net (code "57") (name "unconnected-(U2-CHR0-Pad15)") (class "Default")
      (node (ref "U2") (pin "15") (pinfunction "CHR0_15") (pintype "output+no_connect"))
    )
    (net (code "58") (name "unconnected-(U2-CHR1-Pad14)") (class "Default")
      (node (ref "U2") (pin "14") (pinfunction "CHR1_14") (pintype "output+no_connect"))
    )
    (net (code "59") (name "unconnected-(U2-CHREN-Pad13)") (class "Default")
      (node (ref "U2") (pin "13") (pinfunction "CHREN_13") (pintype "output+no_connect"))
    )
    (net (code "60") (name "unconnected-(U2-CTS-Pad23)") (class "Default")
      (node (ref "U2") (pin "23") (pinfunction "CTS_23") (pintype "input+no_connect"))
    )
    (net (code "61") (name "unconnected-(U2-DCD-Pad1)") (class "Default")
      (node (ref "U2") (pin "1") (pinfunction "DCD_1") (pintype "input+no_connect"))
    )
    (net (code "62") (name "unconnected-(U2-DSR-Pad27)") (class "Default")
      (node (ref "U2") (pin "27") (pinfunction "DSR_27") (pintype "input+no_connect"))
    )
    (net (code "63") (name "unconnected-(U2-GPIO.0{slash}TXT-Pad19)") (class "Default")
      (node (ref "U2") (pin "19") (pinfunction "GPIO.0/TXT_19") (pintype "bidirectional+no_connect"))
    )
    (net (code "64") (name "unconnected-(U2-GPIO.1{slash}RXT-Pad18)") (class "Default")
      (node (ref "U2") (pin "18") (pinfunction "GPIO.1/RXT_18") (pintype "bidirectional+no_connect"))
    )
    (net (code "65") (name "unconnected-(U2-GPIO.2{slash}RS485-Pad17)") (class "Default")
      (node (ref "U2") (pin "17") (pinfunction "GPIO.2/RS485_17") (pintype "bidirectional+no_connect"))
    )
    (net (code "66") (name "unconnected-(U2-GPIO.3{slash}WAKEUP-Pad16)") (class "Default")
      (node (ref "U2") (pin "16") (pinfunction "GPIO.3/WAKEUP_16") (pintype "bidirectional+no_connect"))
    )
    (net (code "67") (name "unconnected-(U2-GPIO.4-Pad22)") (class "Default")
      (node (ref "U2") (pin "22") (pinfunction "GPIO.4_22") (pintype "bidirectional+no_connect"))
    )
    (net (code "68") (name "unconnected-(U2-GPIO.5-Pad21)") (class "Default")
      (node (ref "U2") (pin "21") (pinfunction "GPIO.5_21") (pintype "bidirectional+no_connect"))
    )
    (net (code "69") (name "unconnected-(U2-GPIO.6-Pad20)") (class "Default")
      (node (ref "U2") (pin "20") (pinfunction "GPIO.6_20") (pintype "bidirectional+no_connect"))
    )
    (net (code "70") (name "unconnected-(U2-NC-Pad10)") (class "Default")
      (node (ref "U2") (pin "10") (pinfunction "NC_10") (pintype "passive+no_connect"))
    )
    (net (code "71") (name "unconnected-(U2-SUSPEND-Pad12)") (class "Default")
      (node (ref "U2") (pin "12") (pinfunction "SUSPEND_12") (pintype "output+no_connect"))
    )
    (net (code "72") (name "unconnected-(U2-~{RI}{slash}CLK-Pad2)") (class "Default")
      (node (ref "U2") (pin "2") (pinfunction "~{RI}/CLK_2") (pintype "bidirectional+no_connect"))
    )
  )
)
